# V1_0.net
KiCad netlist of a schematic drawn in Altium Designer
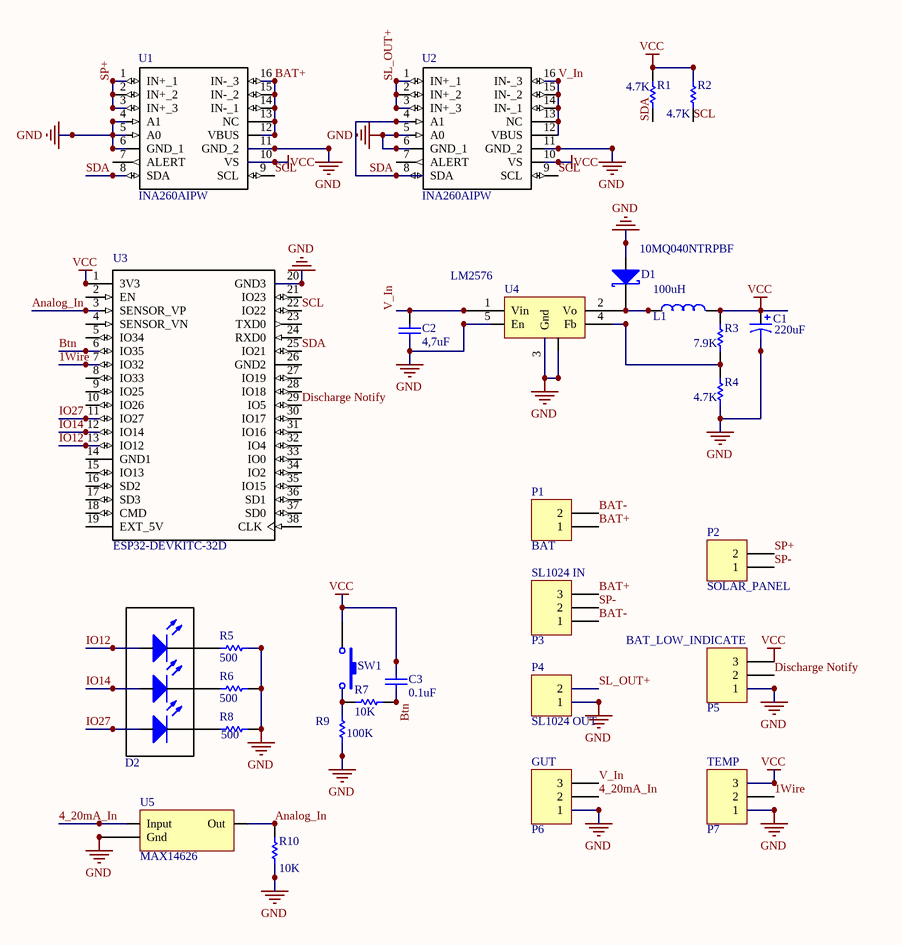
[diagram p0: V1_0.SchDoc]

(export (version "E")
  (design (tool "Eeschema 10.0.6"))
  (components
    (comp (ref "C1")
      (value "220uF")
      (footprint "Cap:Capacitor -Tantalum E size SMD")
      (fields (field (name "TOLERANCE") "+-10%") (field (name "Comment") "Capacitor Tantalum"))
      (libsource (lib "Cap") (part "Cap_tantal"))
    )
    (comp (ref "C2")
      (value "4,7uF")
      (footprint "CAPC3225L")
      (description "Capacitor (Semiconductor SIM Model)")
      (fields
        (field (name "TOLERANCE") "+-10%")
        (field (name "Comment") "Ceramic Capacitor")
        (field (name "PUBLISHER") "Altium Limited")
      )
      (libsource (lib "Miscellaneous Devices") (part "Cap Semi"))
    )
    (comp (ref "C3")
      (value "0.1uF")
      (footprint "CAP 0603")
      (description "Capacitor")
      (libsource (lib "Capacitor") (part "Capacitor"))
    )
    (comp (ref "D1")
      (value "Diode Schottky")
      (footprint "DIOM4427X20N")
      (fields
        (field (name "NAME") "10MQ040NTRPBF")
        (field (name "MANUFACTURER") "International Rectifier")
        (field (name "PARTNUMBER") "10MQ040NTRPBF")
      )
      (libsource (lib "Diode_sh") (part "Shotky_Diode"))
    )
    (comp (ref "D2") (value "RGB 5050") (footprint "LED 5050") (libsource (lib "5050 RGB") (part "RGB 5050")))
    (comp (ref "L1")
      (value "100uH")
      (footprint "CDRH127")
      (description "Inductor")
      (fields (field (name "PARTNUMBER") "CDRH127/LD") (field (name "MANUFACTURER") "Sumida"))
      (libsource (lib "Coil") (part "Coil"))
    )
    (comp (ref "P1")
      (value "BAT")
      (footprint "DG301_2pin")
      (description "DG301")
      (libsource (lib "KLS2") (part "2_pin"))
    )
    (comp (ref "P2")
      (value "SOLAR_PANEL")
      (footprint "DG301_2pin")
      (description "DG301")
      (libsource (lib "KLS2") (part "2_pin"))
    )
    (comp (ref "P3")
      (value "SL1024 IN")
      (footprint "DG301_3pin")
      (description "DG301")
      (libsource (lib "KLS2") (part "3_PIN"))
    )
    (comp (ref "P4")
      (value "SL1024 OUT")
      (footprint "DG301_2pin")
      (description "DG301")
      (libsource (lib "KLS2") (part "2_pin"))
    )
    (comp (ref "P5")
      (value "BAT_LOW_INDICATE")
      (footprint "DG301_3pin")
      (description "DG301")
      (libsource (lib "KLS2") (part "3_PIN"))
    )
    (comp (ref "P6")
      (value "GUT")
      (footprint "DG301_3pin")
      (description "DG301")
      (libsource (lib "KLS2") (part "3_PIN"))
    )
    (comp (ref "P7")
      (value "TEMP")
      (footprint "DG301_3pin")
      (description "DG301")
      (libsource (lib "KLS2") (part "3_PIN"))
    )
    (comp (ref "R1")
      (value "4.7K")
      (footprint "RES1608")
      (description "Semiconductor Resistor")
      (fields (field (name "PUBLISHER") "Altium Limited"))
      (libsource (lib "Miscellaneous Devices") (part "Resistor_SMD"))
    )
    (comp (ref "R2")
      (value "4.7K")
      (footprint "RES1608")
      (description "Semiconductor Resistor")
      (fields (field (name "PUBLISHER") "Altium Limited"))
      (libsource (lib "Miscellaneous Devices") (part "Resistor_SMD"))
    )
    (comp (ref "R3")
      (value "7.9K")
      (footprint "RES1608")
      (description "Semiconductor Resistor")
      (fields (field (name "PUBLISHER") "Altium Limited"))
      (libsource (lib "Miscellaneous Devices") (part "Resistor_SMD"))
    )
    (comp (ref "R4")
      (value "4.7K")
      (footprint "RES1608")
      (description "Semiconductor Resistor")
      (fields (field (name "PUBLISHER") "Altium Limited"))
      (libsource (lib "Miscellaneous Devices") (part "Resistor_SMD"))
    )
    (comp (ref "R5")
      (value "500")
      (footprint "RES1608")
      (description "Semiconductor Resistor")
      (fields (field (name "PUBLISHER") "Altium Limited"))
      (libsource (lib "Miscellaneous Devices") (part "Resistor_SMD"))
    )
    (comp (ref "R6")
      (value "500")
      (footprint "RES1608")
      (description "Semiconductor Resistor")
      (fields (field (name "PUBLISHER") "Altium Limited"))
      (libsource (lib "Miscellaneous Devices") (part "Resistor_SMD"))
    )
    (comp (ref "R7")
      (value "10K")
      (footprint "RES1608")
      (description "Semiconductor Resistor")
      (fields (field (name "PUBLISHER") "Altium Limited"))
      (libsource (lib "Miscellaneous Devices") (part "Resistor_SMD"))
    )
    (comp (ref "R8")
      (value "500")
      (footprint "RES1608")
      (description "Semiconductor Resistor")
      (fields (field (name "PUBLISHER") "Altium Limited"))
      (libsource (lib "Miscellaneous Devices") (part "Resistor_SMD"))
    )
    (comp (ref "R9")
      (value "100K")
      (footprint "RES1608")
      (description "Semiconductor Resistor")
      (fields (field (name "PUBLISHER") "Altium Limited"))
      (libsource (lib "Miscellaneous Devices") (part "Resistor_SMD"))
    )
    (comp (ref "R10")
      (value "10K")
      (footprint "RESC3216L")
      (description "Semiconductor Resistor")
      (fields
        (field (name "TOLERANCE") "+-5%")
        (field (name "Comment") "Resistor")
        (field (name "PUBLISHER") "Altium Limited")
      )
      (libsource (lib "Miscellaneous Devices") (part "Res Semi"))
    )
    (comp (ref "SW1") (value "SW-34") (footprint "SW-34") (libsource (lib "SWT-34") (part "SW-34")))
    (comp (ref "U1")
      (value "INA260AIPW")
      (footprint "SamacSys:SOP65P640X120-16N")
      (description "Integrated Circuit")
      (fields (field (name "MOUSER PART NUMBER") "595-INA260AIPW"))
      (libsource (lib "*") (part "INA260AIPW"))
    )
    (comp (ref "U2")
      (value "INA260AIPW")
      (footprint "SamacSys:SOP65P640X120-16N")
      (description "Integrated Circuit")
      (fields (field (name "MOUSER PART NUMBER") "595-INA260AIPW"))
      (libsource (lib "*") (part "INA260AIPW"))
    )
    (comp (ref "U3")
      (value "ESP32-DEVKITC-32D")
      (footprint "*MODULE_ESP32-DEVKITC-32D")
      (description "Eval Board For Esp-Wroom-32")
      (fields (field (name "MF") "Espressif Systems"))
      (libsource (lib "ESP32-DEVKITC-32D") (part "ESP32-DEVKITC-32D"))
    )
    (comp (ref "U4")
      (value "IC")
      (footprint "TO170P1435X450-6N - duplicate")
      (fields (field (name "MANUFACTURER") "TEXAS INSTRUMENTS") (field (name "PARTNUMBER") "LM2576"))
      (libsource (lib "LM2575") (part "LM2575"))
    )
    (comp (ref "U5")
      (value "MAX14626")
      (footprint "TDFN-6")
      (description "4–20mA  Current Loop Protector")
      (libsource (lib "MAX14626") (part "MAX14626"))
    )
  )
  (nets
    (net (code "1") (name "/1Wire") (class "Default")
      (node (ref "P7") (pin "2") (pinfunction "2_2") (pintype "passive"))
      (node (ref "U3") (pin "7") (pinfunction "IO32_7") (pintype "bidirectional"))
    )
    (net (code "2") (name "/4_20mA_In") (class "Default")
      (node (ref "P6") (pin "2") (pinfunction "2_2") (pintype "passive"))
      (node (ref "U5") (pin "1") (pinfunction "Input_1") (pintype "passive"))
    )
    (net (code "3") (name "/Analog_In") (class "Default")
      (node (ref "R10") (pin "2") (pinfunction "2_2") (pintype "passive"))
      (node (ref "U3") (pin "3") (pinfunction "SENSOR_VP_3") (pintype "input"))
      (node (ref "U5") (pin "6") (pinfunction "Out_6") (pintype "passive"))
    )
    (net (code "4") (name "/BAT+") (class "Default")
      (node (ref "P1") (pin "1") (pinfunction "1_1") (pintype "passive"))
      (node (ref "P3") (pin "3") (pinfunction "3_3") (pintype "passive"))
      (node (ref "U1") (pin "12") (pinfunction "VBUS_12") (pintype "power_in"))
      (node (ref "U1") (pin "13") (pinfunction "NC_13") (pintype "passive"))
      (node (ref "U1") (pin "14") (pinfunction "IN-_1_14") (pintype "bidirectional"))
      (node (ref "U1") (pin "15") (pinfunction "IN-_2_15") (pintype "bidirectional"))
      (node (ref "U1") (pin "16") (pinfunction "IN-_3_16") (pintype "bidirectional"))
    )
    (net (code "5") (name "/BAT-") (class "Default")
      (node (ref "P1") (pin "2") (pinfunction "2_2") (pintype "passive"))
      (node (ref "P3") (pin "1") (pinfunction "1_1") (pintype "passive"))
    )
    (net (code "6") (name "/Btn") (class "Default")
      (node (ref "C3") (pin "1") (pinfunction "1_1") (pintype "passive"))
      (node (ref "R7") (pin "2") (pinfunction "2_2") (pintype "passive"))
      (node (ref "U3") (pin "6") (pinfunction "IO35_6") (pintype "bidirectional"))
    )
    (net (code "7") (name "/Discharge Notify") (class "Default")
      (node (ref "P5") (pin "2") (pinfunction "2_2") (pintype "passive"))
      (node (ref "U3") (pin "29") (pinfunction "IO5_29") (pintype "bidirectional"))
    )
    (net (code "8") (name "/IO12") (class "Default")
      (node (ref "D2") (pin "1") (pintype "passive"))
      (node (ref "U3") (pin "13") (pinfunction "IO12_13") (pintype "bidirectional"))
    )
    (net (code "9") (name "/IO14") (class "Default")
      (node (ref "D2") (pin "2") (pintype "passive"))
      (node (ref "U3") (pin "12") (pinfunction "IO14_12") (pintype "bidirectional"))
    )
    (net (code "10") (name "/IO27") (class "Default")
      (node (ref "D2") (pin "3") (pintype "passive"))
      (node (ref "U3") (pin "11") (pinfunction "IO27_11") (pintype "bidirectional"))
    )
    (net (code "11") (name "/SCL") (class "Default")
      (node (ref "R2") (pin "1") (pinfunction "1_1") (pintype "passive"))
      (node (ref "U1") (pin "9") (pinfunction "SCL_9") (pintype "bidirectional"))
      (node (ref "U2") (pin "9") (pinfunction "SCL_9") (pintype "bidirectional"))
      (node (ref "U3") (pin "22") (pinfunction "IO22_22") (pintype "bidirectional"))
    )
    (net (code "12") (name "/SDA") (class "Default")
      (node (ref "R1") (pin "1") (pinfunction "1_1") (pintype "passive"))
      (node (ref "U1") (pin "8") (pinfunction "SDA_8") (pintype "bidirectional"))
      (node (ref "U2") (pin "4") (pinfunction "A1_4") (pintype "input"))
      (node (ref "U2") (pin "8") (pinfunction "SDA_8") (pintype "bidirectional"))
      (node (ref "U3") (pin "25") (pinfunction "IO21_25") (pintype "bidirectional"))
    )
    (net (code "13") (name "/SL_OUT+") (class "Default")
      (node (ref "P4") (pin "2") (pinfunction "2_2") (pintype "passive"))
      (node (ref "U2") (pin "1") (pinfunction "IN+_1_1") (pintype "bidirectional"))
      (node (ref "U2") (pin "2") (pinfunction "IN+_2_2") (pintype "bidirectional"))
      (node (ref "U2") (pin "3") (pinfunction "IN+_3_3") (pintype "bidirectional"))
    )
    (net (code "14") (name "/SP+") (class "Default")
      (node (ref "P2") (pin "2") (pinfunction "2_2") (pintype "passive"))
      (node (ref "U1") (pin "1") (pinfunction "IN+_1_1") (pintype "bidirectional"))
      (node (ref "U1") (pin "2") (pinfunction "IN+_2_2") (pintype "bidirectional"))
      (node (ref "U1") (pin "3") (pinfunction "IN+_3_3") (pintype "bidirectional"))
    )
    (net (code "15") (name "/SP-") (class "Default")
      (node (ref "P2") (pin "1") (pinfunction "1_1") (pintype "passive"))
      (node (ref "P3") (pin "2") (pinfunction "2_2") (pintype "passive"))
    )
    (net (code "16") (name "/V_In") (class "Default")
      (node (ref "C2") (pin "2") (pinfunction "2_2") (pintype "passive"))
      (node (ref "P6") (pin "3") (pinfunction "3_3") (pintype "passive"))
      (node (ref "U2") (pin "12") (pinfunction "VBUS_12") (pintype "power_in"))
      (node (ref "U2") (pin "13") (pinfunction "NC_13") (pintype "passive"))
      (node (ref "U2") (pin "14") (pinfunction "IN-_1_14") (pintype "bidirectional"))
      (node (ref "U2") (pin "15") (pinfunction "IN-_2_15") (pintype "bidirectional"))
      (node (ref "U2") (pin "16") (pinfunction "IN-_3_16") (pintype "bidirectional"))
      (node (ref "U4") (pin "1") (pinfunction "Vin_1") (pintype "power_in"))
    )
    (net (code "17") (name "GND") (class "Default")
      (node (ref "C1") (pin "1") (pinfunction "1_1") (pintype "passive"))
      (node (ref "C2") (pin "1") (pinfunction "1_1") (pintype "passive"))
      (node (ref "D1") (pin "2") (pinfunction "A_2") (pintype "passive"))
      (node (ref "P4") (pin "1") (pinfunction "1_1") (pintype "passive"))
      (node (ref "P5") (pin "1") (pinfunction "1_1") (pintype "passive"))
      (node (ref "P6") (pin "1") (pinfunction "1_1") (pintype "passive"))
      (node (ref "P7") (pin "1") (pinfunction "1_1") (pintype "passive"))
      (node (ref "R10") (pin "1") (pinfunction "1_1") (pintype "passive"))
      (node (ref "R4") (pin "1") (pinfunction "1_1") (pintype "passive"))
      (node (ref "R5") (pin "1") (pinfunction "1_1") (pintype "passive"))
      (node (ref "R6") (pin "1") (pinfunction "1_1") (pintype "passive"))
      (node (ref "R8") (pin "1") (pinfunction "1_1") (pintype "passive"))
      (node (ref "R9") (pin "2") (pinfunction "2_2") (pintype "passive"))
      (node (ref "U1") (pin "11") (pinfunction "GND_2_11") (pintype "power_in"))
      (node (ref "U1") (pin "4") (pinfunction "A1_4") (pintype "input"))
      (node (ref "U1") (pin "5") (pinfunction "A0_5") (pintype "input"))
      (node (ref "U1") (pin "6") (pinfunction "GND_1_6") (pintype "power_in"))
      (node (ref "U2") (pin "11") (pinfunction "GND_2_11") (pintype "power_in"))
      (node (ref "U2") (pin "5") (pinfunction "A0_5") (pintype "input"))
      (node (ref "U2") (pin "6") (pinfunction "GND_1_6") (pintype "power_in"))
      (node (ref "U3") (pin "20") (pinfunction "GND3_20") (pintype "power_in"))
      (node (ref "U4") (pin "3") (pinfunction "Gnd_3") (pintype "passive"))
      (node (ref "U4") (pin "5") (pinfunction "En_5") (pintype "passive"))
      (node (ref "U4") (pin "6") (pinfunction "Gnd_6") (pintype "passive"))
      (node (ref "U5") (pin "2") (pinfunction "NC_2") (pintype "passive"))
      (node (ref "U5") (pin "3") (pinfunction "NC_3") (pintype "passive"))
      (node (ref "U5") (pin "4") (pinfunction "NC_4") (pintype "passive"))
      (node (ref "U5") (pin "5") (pinfunction "Gnd_5") (pintype "passive"))
      (node (ref "U5") (pin "7") (pinfunction "NC_7") (pintype "passive"))
    )
    (net (code "18") (name "Net-(D1-K)") (class "Default")
      (node (ref "D1") (pin "1") (pinfunction "K_1") (pintype "passive"))
      (node (ref "L1") (pin "2") (pintype "passive"))
      (node (ref "U4") (pin "2") (pinfunction "Vo_2") (pintype "power_in"))
    )
    (net (code "19") (name "Net-(D2-Pad4)") (class "Default")
      (node (ref "D2") (pin "4") (pintype "passive"))
      (node (ref "R5") (pin "2") (pinfunction "2_2") (pintype "passive"))
    )
    (net (code "20") (name "Net-(D2-Pad5)") (class "Default")
      (node (ref "D2") (pin "5") (pintype "passive"))
      (node (ref "R6") (pin "2") (pinfunction "2_2") (pintype "passive"))
    )
    (net (code "21") (name "Net-(D2-Pad6)") (class "Default")
      (node (ref "D2") (pin "6") (pintype "passive"))
      (node (ref "R8") (pin "2") (pinfunction "2_2") (pintype "passive"))
    )
    (net (code "22") (name "Net-(R7-Pad1)") (class "Default")
      (node (ref "R7") (pin "1") (pinfunction "1_1") (pintype "passive"))
      (node (ref "R9") (pin "1") (pinfunction "1_1") (pintype "passive"))
      (node (ref "SW1") (pin "2") (pinfunction "2_2") (pintype "passive"))
    )
    (net (code "23") (name "Net-(U4-Fb)") (class "Default")
      (node (ref "R3") (pin "1") (pinfunction "1_1") (pintype "passive"))
      (node (ref "R4") (pin "2") (pinfunction "2_2") (pintype "passive"))
      (node (ref "U4") (pin "4") (pinfunction "Fb_4") (pintype "passive"))
    )
    (net (code "24") (name "VCC") (class "Default")
      (node (ref "C1") (pin "2") (pinfunction "2_2") (pintype "passive"))
      (node (ref "C3") (pin "2") (pinfunction "2_2") (pintype "passive"))
      (node (ref "L1") (pin "1") (pintype "passive"))
      (node (ref "P5") (pin "3") (pinfunction "3_3") (pintype "passive"))
      (node (ref "P7") (pin "3") (pinfunction "3_3") (pintype "passive"))
      (node (ref "R1") (pin "2") (pinfunction "2_2") (pintype "passive"))
      (node (ref "R2") (pin "2") (pinfunction "2_2") (pintype "passive"))
      (node (ref "R3") (pin "2") (pinfunction "2_2") (pintype "passive"))
      (node (ref "SW1") (pin "1") (pinfunction "1_1") (pintype "passive"))
      (node (ref "U1") (pin "10") (pinfunction "VS_10") (pintype "power_in"))
      (node (ref "U2") (pin "10") (pinfunction "VS_10") (pintype "power_in"))
      (node (ref "U3") (pin "1") (pinfunction "3V3_1") (pintype "power_in"))
    )
    (net (code "25") (name "unconnected-(U1-ALERT-Pad7)") (class "Default")
      (node (ref "U1") (pin "7") (pinfunction "ALERT_7") (pintype "output"))
    )
    (net (code "26") (name "unconnected-(U2-ALERT-Pad7)") (class "Default")
      (node (ref "U2") (pin "7") (pinfunction "ALERT_7") (pintype "output"))
    )
    (net (code "27") (name "unconnected-(U3-CLK-Pad38)") (class "Default")
      (node (ref "U3") (pin "38") (pinfunction "CLK_38") (pintype "input"))
    )
    (net (code "28") (name "unconnected-(U3-CMD-Pad18)") (class "Default")
      (node (ref "U3") (pin "18") (pinfunction "CMD_18") (pintype "bidirectional"))
    )
    (net (code "29") (name "unconnected-(U3-EN-Pad2)") (class "Default")
      (node (ref "U3") (pin "2") (pinfunction "EN_2") (pintype "input"))
    )
    (net (code "30") (name "unconnected-(U3-EXT_5V-Pad19)") (class "Default")
      (node (ref "U3") (pin "19") (pinfunction "EXT_5V_19") (pintype "power_in"))
    )
    (net (code "31") (name "unconnected-(U3-GND1-Pad14)") (class "Default")
      (node (ref "U3") (pin "14") (pinfunction "GND1_14") (pintype "power_in"))
    )
    (net (code "32") (name "unconnected-(U3-GND2-Pad26)") (class "Default")
      (node (ref "U3") (pin "26") (pinfunction "GND2_26") (pintype "power_in"))
    )
    (net (code "33") (name "unconnected-(U3-IO0-Pad33)") (class "Default")
      (node (ref "U3") (pin "33") (pinfunction "IO0_33") (pintype "bidirectional"))
    )
    (net (code "34") (name "unconnected-(U3-IO2-Pad34)") (class "Default")
      (node (ref "U3") (pin "34") (pinfunction "IO2_34") (pintype "bidirectional"))
    )
    (net (code "35") (name "unconnected-(U3-IO4-Pad32)") (class "Default")
      (node (ref "U3") (pin "32") (pinfunction "IO4_32") (pintype "bidirectional"))
    )
    (net (code "36") (name "unconnected-(U3-IO13-Pad15)") (class "Default")
      (node (ref "U3") (pin "15") (pinfunction "IO13_15") (pintype "bidirectional"))
    )
    (net (code "37") (name "unconnected-(U3-IO15-Pad35)") (class "Default")
      (node (ref "U3") (pin "35") (pinfunction "IO15_35") (pintype "bidirectional"))
    )
    (net (code "38") (name "unconnected-(U3-IO16-Pad31)") (class "Default")
      (node (ref "U3") (pin "31") (pinfunction "IO16_31") (pintype "bidirectional"))
    )
    (net (code "39") (name "unconnected-(U3-IO17-Pad30)") (class "Default")
      (node (ref "U3") (pin "30") (pinfunction "IO17_30") (pintype "bidirectional"))
    )
    (net (code "40") (name "unconnected-(U3-IO18-Pad28)") (class "Default")
      (node (ref "U3") (pin "28") (pinfunction "IO18_28") (pintype "bidirectional"))
    )
    (net (code "41") (name "unconnected-(U3-IO19-Pad27)") (class "Default")
      (node (ref "U3") (pin "27") (pinfunction "IO19_27") (pintype "bidirectional"))
    )
    (net (code "42") (name "unconnected-(U3-IO23-Pad21)") (class "Default")
      (node (ref "U3") (pin "21") (pinfunction "IO23_21") (pintype "bidirectional"))
    )
    (net (code "43") (name "unconnected-(U3-IO25-Pad9)") (class "Default")
      (node (ref "U3") (pin "9") (pinfunction "IO25_9") (pintype "bidirectional"))
    )
    (net (code "44") (name "unconnected-(U3-IO26-Pad10)") (class "Default")
      (node (ref "U3") (pin "10") (pinfunction "IO26_10") (pintype "bidirectional"))
    )
    (net (code "45") (name "unconnected-(U3-IO33-Pad8)") (class "Default")
      (node (ref "U3") (pin "8") (pinfunction "IO33_8") (pintype "bidirectional"))
    )
    (net (code "46") (name "unconnected-(U3-IO34-Pad5)") (class "Default")
      (node (ref "U3") (pin "5") (pinfunction "IO34_5") (pintype "bidirectional"))
    )
    (net (code "47") (name "unconnected-(U3-RXD0-Pad24)") (class "Default")
      (node (ref "U3") (pin "24") (pinfunction "RXD0_24") (pintype "input"))
    )
    (net (code "48") (name "unconnected-(U3-SD0-Pad37)") (class "Default")
      (node (ref "U3") (pin "37") (pinfunction "SD0_37") (pintype "bidirectional"))
    )
    (net (code "49") (name "unconnected-(U3-SD1-Pad36)") (class "Default")
      (node (ref "U3") (pin "36") (pinfunction "SD1_36") (pintype "bidirectional"))
    )
    (net (code "50") (name "unconnected-(U3-SD2-Pad16)") (class "Default")
      (node (ref "U3") (pin "16") (pinfunction "SD2_16") (pintype "bidirectional"))
    )
    (net (code "51") (name "unconnected-(U3-SD3-Pad17)") (class "Default")
      (node (ref "U3") (pin "17") (pinfunction "SD3_17") (pintype "bidirectional"))
    )
    (net (code "52") (name "unconnected-(U3-SENSOR_VN-Pad4)") (class "Default")
      (node (ref "U3") (pin "4") (pinfunction "SENSOR_VN_4") (pintype "input"))
    )
    (net (code "53") (name "unconnected-(U3-TXD0-Pad23)") (class "Default")
      (node (ref "U3") (pin "23") (pinfunction "TXD0_23") (pintype "output"))
    )
  )
)
